# LSR_GPS_Tracker_Base_Station.net
KiCad netlist of a schematic drawn in EAGLE
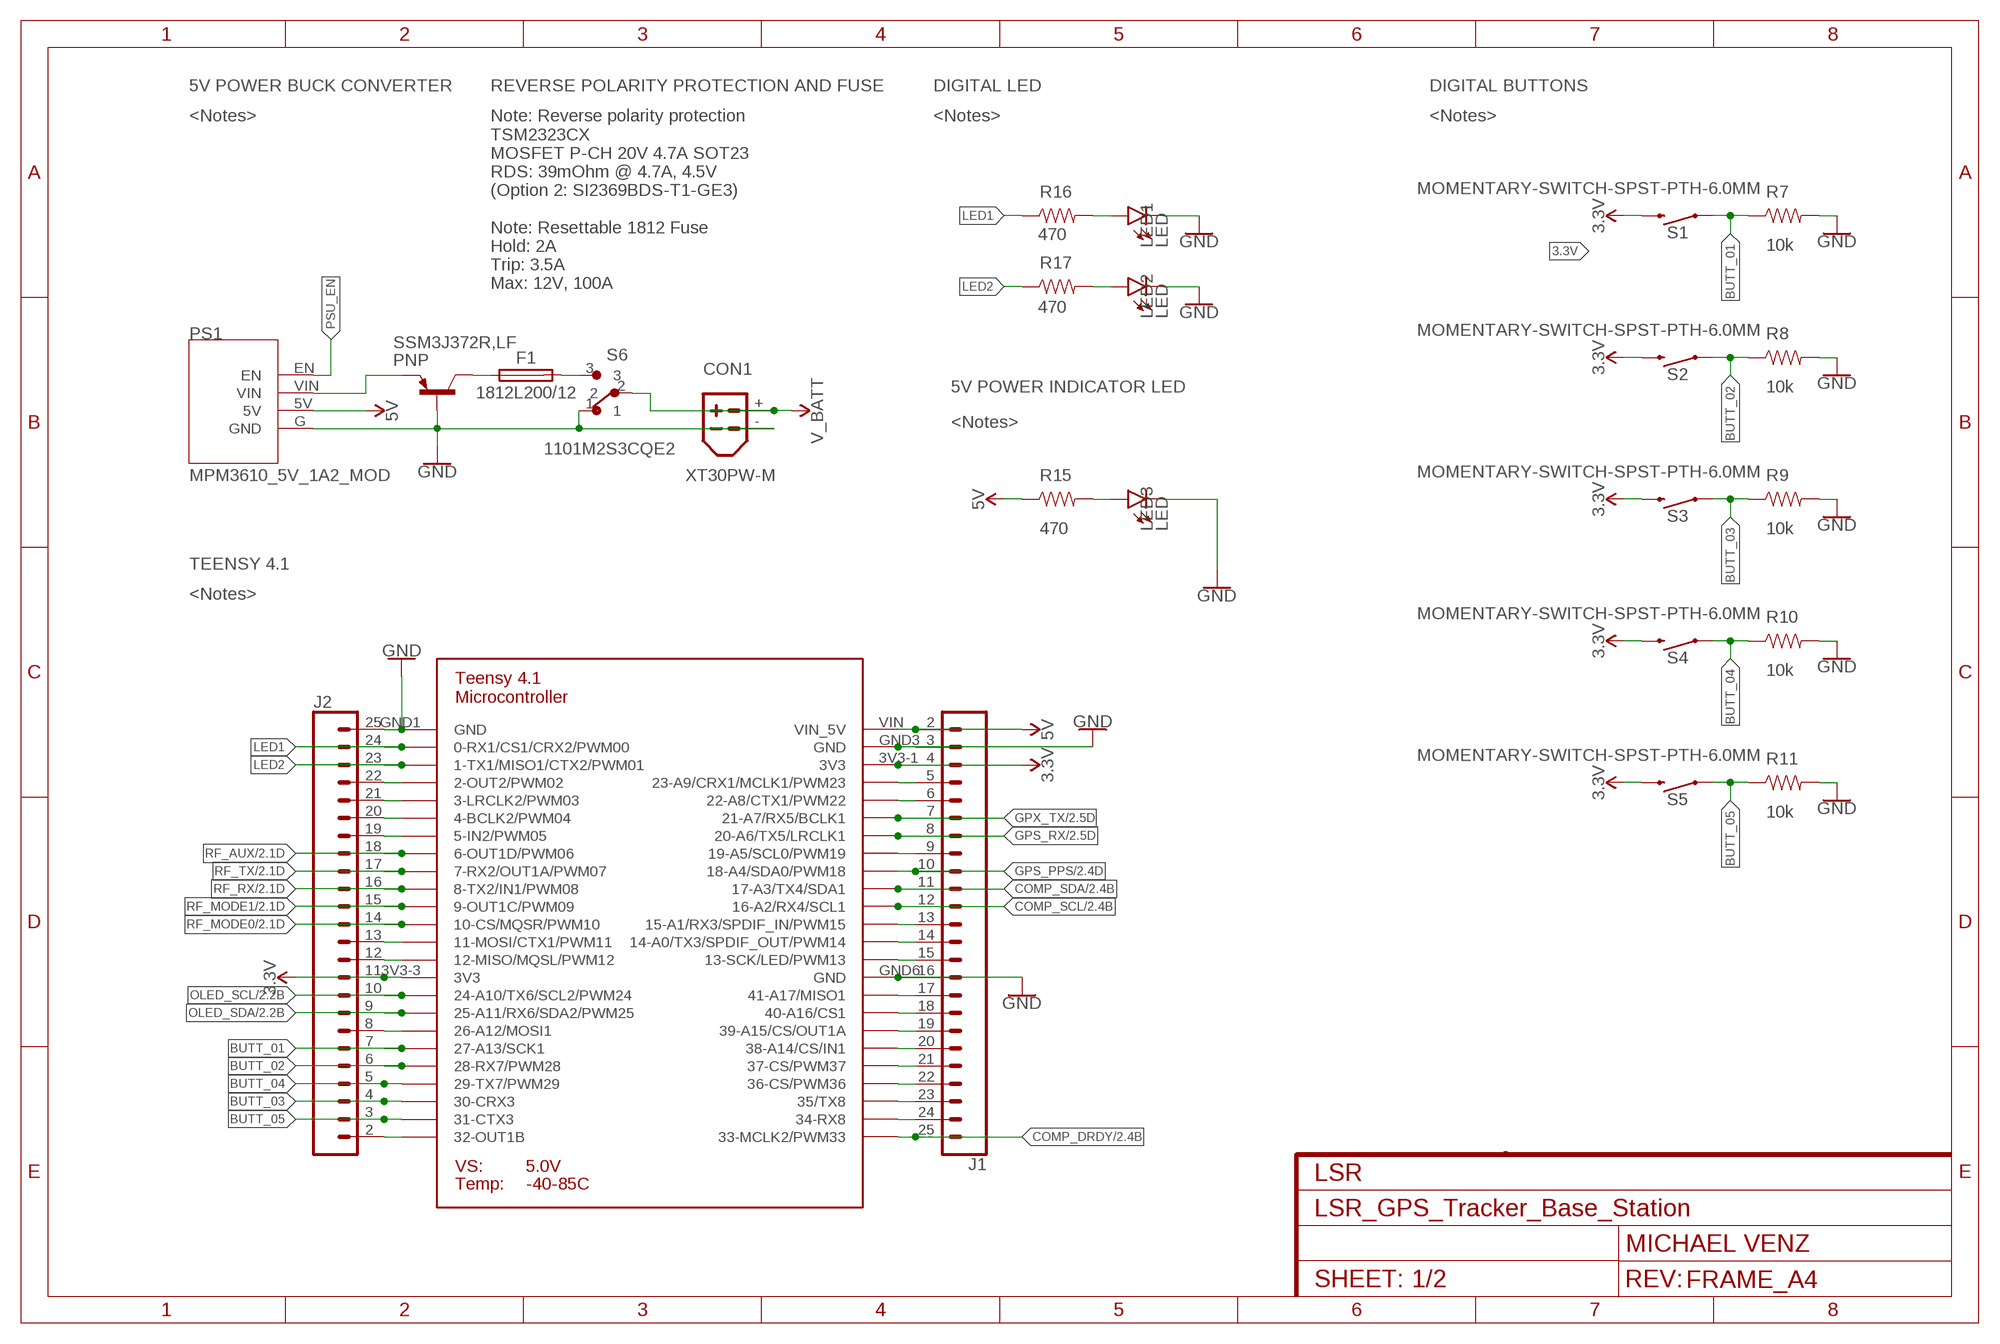
[diagram p0: schematic, sheet 1]
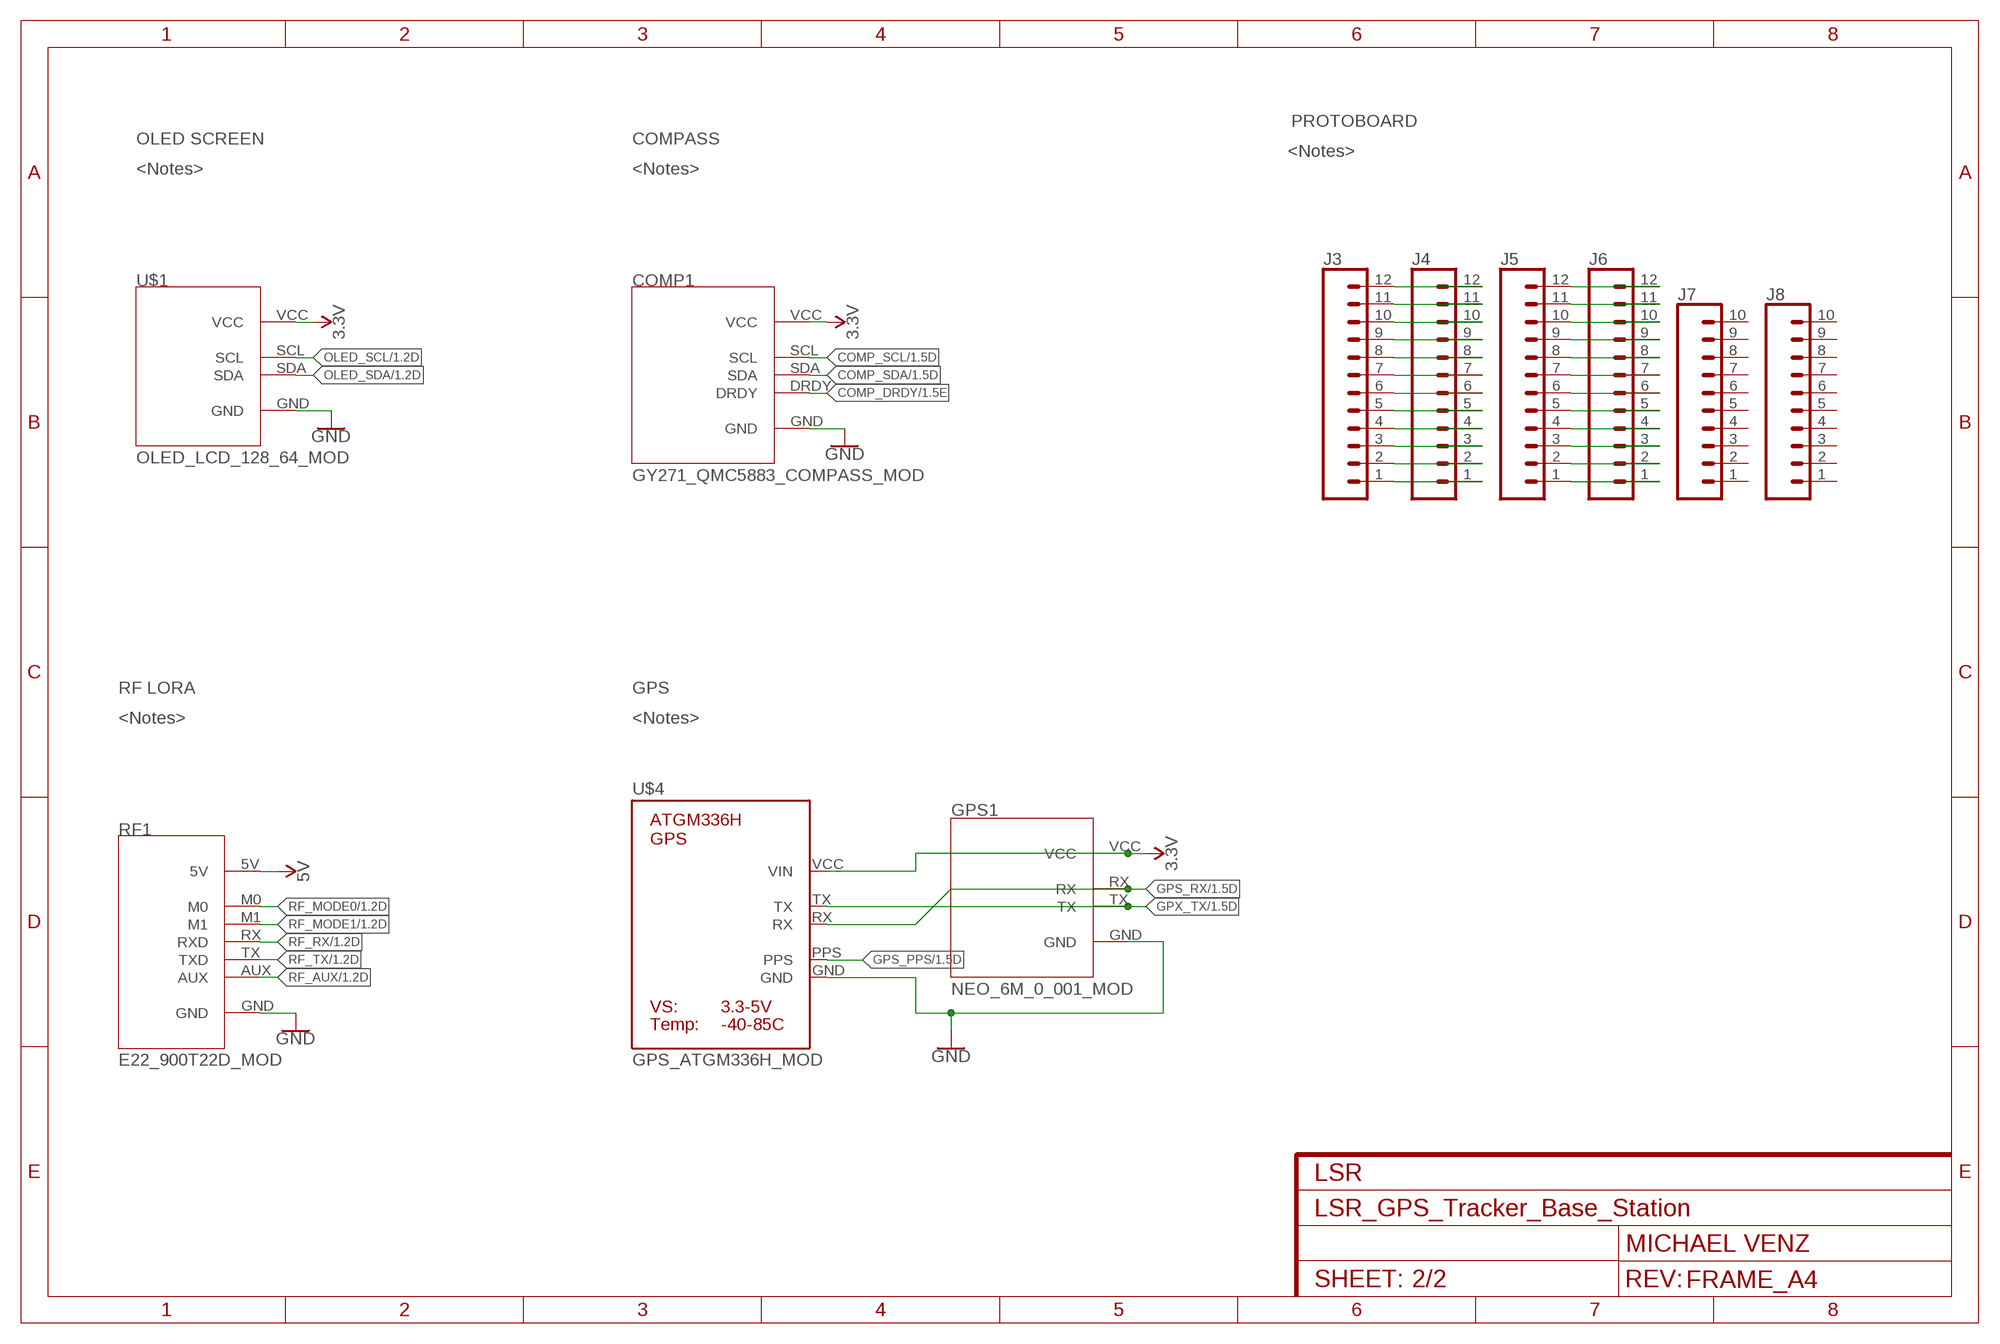
[diagram p1: schematic, sheet 2]

(export (version "E")
  (design (tool "Eeschema 10.0.6"))
  (components
    (comp (ref "CON1")
      (value "XT30PW-M")
      (footprint "eagle-import:XT30PW-PLUG")
      (libsource (lib "eagle-import") (part "XT30PW-M"))
    )
    (comp (ref "F1")
      (value "1812L200/12")
      (footprint "eagle-import:FUSC4532X125")
      (fields (field (name "MANUFACTURER") "Littlefuse"))
      (libsource (lib "eagle-import") (part "1812L200/12"))
    )
    (comp (ref "J1")
      (value "CONN_24")
      (footprint "eagle-import:1X24")
      (libsource (lib "eagle-import") (part "CONN_24"))
    )
    (comp (ref "J2")
      (value "CONN_24")
      (footprint "eagle-import:1X24")
      (libsource (lib "eagle-import") (part "CONN_24"))
    )
    (comp (ref "LED1")
      (value "LED")
      (footprint "eagle-import:0805_LED")
      (libsource (lib "eagle-import") (part "LED"))
    )
    (comp (ref "LED2")
      (value "LED")
      (footprint "eagle-import:0805_LED")
      (libsource (lib "eagle-import") (part "LED"))
    )
    (comp (ref "LED3")
      (value "LED")
      (footprint "eagle-import:0805_LED")
      (libsource (lib "eagle-import") (part "LED"))
    )
    (comp (ref "PS1")
      (value "MPM3610_5V_1A2_MOD")
      (footprint "eagle-import:MPM3610_5V_1A2_FP")
      (libsource (lib "eagle-import") (part "MPM3610_5V_1A2_MOD"))
    )
    (comp (ref "R7")
      (value "10k")
      (footprint "eagle-import:0805_RESISTOR_FP")
      (libsource (lib "eagle-import") (part "0805_RESISTOR"))
    )
    (comp (ref "R8")
      (value "10k")
      (footprint "eagle-import:0805_RESISTOR_FP")
      (libsource (lib "eagle-import") (part "0805_RESISTOR"))
    )
    (comp (ref "R9")
      (value "10k")
      (footprint "eagle-import:0805_RESISTOR_FP")
      (libsource (lib "eagle-import") (part "0805_RESISTOR"))
    )
    (comp (ref "R10")
      (value "10k")
      (footprint "eagle-import:0805_RESISTOR_FP")
      (libsource (lib "eagle-import") (part "0805_RESISTOR"))
    )
    (comp (ref "R11")
      (value "10k")
      (footprint "eagle-import:0805_RESISTOR_FP")
      (libsource (lib "eagle-import") (part "0805_RESISTOR"))
    )
    (comp (ref "R15")
      (value "470")
      (footprint "eagle-import:0805_RESISTOR_FP")
      (libsource (lib "eagle-import") (part "0805_RESISTOR"))
    )
    (comp (ref "R16")
      (value "470")
      (footprint "eagle-import:0805_RESISTOR_FP")
      (libsource (lib "eagle-import") (part "0805_RESISTOR"))
    )
    (comp (ref "R17")
      (value "470")
      (footprint "eagle-import:0805_RESISTOR_FP")
      (libsource (lib "eagle-import") (part "0805_RESISTOR"))
    )
    (comp (ref "S1")
      (value "MOMENTARY-SWITCH-SPST-PTH-6.0MM")
      (footprint "eagle-import:TACTILE_SWITCH_PTH_6.0MM")
      (libsource (lib "eagle-import") (part "MOMENTARY-SWITCH-SPST-PTH-6.0MM"))
    )
    (comp (ref "S2")
      (value "MOMENTARY-SWITCH-SPST-PTH-6.0MM")
      (footprint "eagle-import:TACTILE_SWITCH_PTH_6.0MM")
      (libsource (lib "eagle-import") (part "MOMENTARY-SWITCH-SPST-PTH-6.0MM"))
    )
    (comp (ref "S3")
      (value "MOMENTARY-SWITCH-SPST-PTH-6.0MM")
      (footprint "eagle-import:TACTILE_SWITCH_PTH_6.0MM")
      (libsource (lib "eagle-import") (part "MOMENTARY-SWITCH-SPST-PTH-6.0MM"))
    )
    (comp (ref "S4")
      (value "MOMENTARY-SWITCH-SPST-PTH-6.0MM")
      (footprint "eagle-import:TACTILE_SWITCH_PTH_6.0MM")
      (libsource (lib "eagle-import") (part "MOMENTARY-SWITCH-SPST-PTH-6.0MM"))
    )
    (comp (ref "S5")
      (value "MOMENTARY-SWITCH-SPST-PTH-6.0MM")
      (footprint "eagle-import:TACTILE_SWITCH_PTH_6.0MM")
      (libsource (lib "eagle-import") (part "MOMENTARY-SWITCH-SPST-PTH-6.0MM"))
    )
    (comp (ref "S6")
      (value "1101M2S3CQE2")
      (footprint "eagle-import:SW_1101M2S3CQE2")
      (fields (field (name "DIGI-KEY_PART_NUMBER") "CKN5001-ND") (field (name "MF") "C&K"))
      (libsource (lib "eagle-import") (part "1101M2S3CQE2"))
    )
    (comp (ref "SSM3J372R,LF")
      (value "PNP")
      (footprint "eagle-import:SOT95P237X112-3N")
      (libsource (lib "eagle-import") (part "PNPSOT23_"))
    )
    (comp (ref "U$3")
      (value "TEENSY_4_1")
      (footprint "eagle-import:TEENSY_4_1_FP")
      (libsource (lib "eagle-import") (part "TEENSY_4_1"))
    )
    (comp (ref "COMP1")
      (value "GY271_QMC5883_COMPASS_MOD")
      (footprint "eagle-import:GY271_QMC5883_COMPASS_MOD_FP")
      (libsource (lib "eagle-import") (part "GY271_QMC5883_COMPASS_MOD"))
    )
    (comp (ref "GPS1")
      (value "NEO_6M_0_001_MOD")
      (footprint "eagle-import:NEO_6M_0_001_MOD_FP")
      (libsource (lib "eagle-import") (part "NEO_6M_0_001_MOD"))
    )
    (comp (ref "J3")
      (value "CONN_12NO_SILK")
      (footprint "eagle-import:1X12_NO_SILK")
      (libsource (lib "eagle-import") (part "CONN_12NO_SILK"))
    )
    (comp (ref "J4")
      (value "CONN_12NO_SILK")
      (footprint "eagle-import:1X12_NO_SILK")
      (libsource (lib "eagle-import") (part "CONN_12NO_SILK"))
    )
    (comp (ref "J5")
      (value "CONN_12NO_SILK")
      (footprint "eagle-import:1X12_NO_SILK")
      (libsource (lib "eagle-import") (part "CONN_12NO_SILK"))
    )
    (comp (ref "J6")
      (value "CONN_12NO_SILK")
      (footprint "eagle-import:1X12_NO_SILK")
      (libsource (lib "eagle-import") (part "CONN_12NO_SILK"))
    )
    (comp (ref "J7")
      (value "CONN_10NO_SILK_PTH_FEMALE")
      (footprint "eagle-import:1X10_NO_SILK")
      (libsource (lib "eagle-import") (part "CONN_10NO_SILK_PTH_FEMALE"))
    )
    (comp (ref "J8")
      (value "CONN_10NO_SILK_PTH_FEMALE")
      (footprint "eagle-import:1X10_NO_SILK")
      (libsource (lib "eagle-import") (part "CONN_10NO_SILK_PTH_FEMALE"))
    )
    (comp (ref "RF1")
      (value "E22_900T22D_MOD")
      (footprint "eagle-import:E22_900T22D_MOD_FP")
      (libsource (lib "eagle-import") (part "E22_900T22D_MOD"))
    )
    (comp (ref "U$1")
      (value "OLED_LCD_128_64_MOD")
      (footprint "eagle-import:OLED_LCD_128_64_MOD_FP")
      (libsource (lib "eagle-import") (part "OLED_LCD_128_64_MOD"))
    )
    (comp (ref "U$4")
      (value "GPS_ATGM336H_MOD")
      (footprint "eagle-import:GPS_ATGM336H_FP")
      (libsource (lib "eagle-import") (part "GPS_ATGM336H_MOD"))
    )
  )
  (nets
    (net (code "1") (name "3.3V") (class "Default")
      (node (ref "COMP1") (pin "VCC") (pinfunction "VCC_VCC") (pintype "bidirectional"))
      (node (ref "GPS1") (pin "VCC") (pinfunction "VCC_VCC") (pintype "bidirectional"))
      (node (ref "J1") (pin "4") (pinfunction "4_4") (pintype "passive"))
      (node (ref "J2") (pin "11") (pinfunction "11_11") (pintype "passive"))
      (node (ref "S1") (pin "3") (pinfunction "2_3") (pintype "passive"))
      (node (ref "S2") (pin "3") (pinfunction "2_3") (pintype "passive"))
      (node (ref "S3") (pin "3") (pinfunction "2_3") (pintype "passive"))
      (node (ref "S4") (pin "3") (pinfunction "2_3") (pintype "passive"))
      (node (ref "S5") (pin "3") (pinfunction "2_3") (pintype "passive"))
      (node (ref "U$1") (pin "VCC") (pinfunction "VCC_VCC") (pintype "bidirectional"))
      (node (ref "U$3") (pin "3V3-1") (pinfunction "3V3_3V3-1") (pintype "bidirectional"))
      (node (ref "U$3") (pin "3V3-3") (pinfunction "3V3_3V3-3") (pintype "bidirectional"))
      (node (ref "U$4") (pin "VCC") (pinfunction "VIN_VCC") (pintype "bidirectional"))
    )
    (net (code "2") (name "5V") (class "Default")
      (node (ref "J1") (pin "2") (pinfunction "2_2") (pintype "passive"))
      (node (ref "PS1") (pin "5V") (pinfunction "5V_5V") (pintype "bidirectional"))
      (node (ref "R15") (pin "1") (pinfunction "1_1") (pintype "passive"))
      (node (ref "RF1") (pin "5V") (pinfunction "5V_5V") (pintype "bidirectional"))
      (node (ref "U$3") (pin "VIN") (pinfunction "VIN_5V_VIN") (pintype "bidirectional"))
    )
    (net (code "3") (name "BUTT_01") (class "Default")
      (node (ref "J2") (pin "7") (pinfunction "7_7") (pintype "passive"))
      (node (ref "R7") (pin "1") (pinfunction "1_1") (pintype "passive"))
      (node (ref "S1") (pin "1") (pinfunction "1_1") (pintype "passive"))
      (node (ref "U$3") (pin "27-A13/SCK1") (pinfunction "27-A13/SCK1_27-A13/SCK1") (pintype "bidirectional"))
    )
    (net (code "4") (name "BUTT_02") (class "Default")
      (node (ref "J2") (pin "6") (pinfunction "6_6") (pintype "passive"))
      (node (ref "R8") (pin "1") (pinfunction "1_1") (pintype "passive"))
      (node (ref "S2") (pin "1") (pinfunction "1_1") (pintype "passive"))
      (node (ref "U$3") (pin "28-RX7/PWM28") (pinfunction "28-RX7/PWM28_28-RX7/PWM28") (pintype "bidirectional"))
    )
    (net (code "5") (name "BUTT_03") (class "Default")
      (node (ref "J2") (pin "4") (pinfunction "4_4") (pintype "passive"))
      (node (ref "R9") (pin "1") (pinfunction "1_1") (pintype "passive"))
      (node (ref "S3") (pin "1") (pinfunction "1_1") (pintype "passive"))
      (node (ref "U$3") (pin "30-CRX3") (pinfunction "30-CRX3_30-CRX3") (pintype "bidirectional"))
    )
    (net (code "6") (name "BUTT_04") (class "Default")
      (node (ref "J2") (pin "5") (pinfunction "5_5") (pintype "passive"))
      (node (ref "R10") (pin "1") (pinfunction "1_1") (pintype "passive"))
      (node (ref "S4") (pin "1") (pinfunction "1_1") (pintype "passive"))
      (node (ref "U$3") (pin "29-TX7/PWM29") (pinfunction "29-TX7/PWM29_29-TX7/PWM29") (pintype "bidirectional"))
    )
    (net (code "7") (name "BUTT_05") (class "Default")
      (node (ref "J2") (pin "3") (pinfunction "3_3") (pintype "passive"))
      (node (ref "R11") (pin "1") (pinfunction "1_1") (pintype "passive"))
      (node (ref "S5") (pin "1") (pinfunction "1_1") (pintype "passive"))
      (node (ref "U$3") (pin "31-CTX3") (pinfunction "31-CTX3_31-CTX3") (pintype "bidirectional"))
    )
    (net (code "8") (name "COMP_DRDY") (class "Default")
      (node (ref "COMP1") (pin "DRDY") (pinfunction "DRDY_DRDY") (pintype "bidirectional"))
      (node (ref "J1") (pin "25") (pinfunction "25_25") (pintype "passive"))
      (node (ref "U$3") (pin "33-MCLK2/PWM33") (pinfunction "33-MCLK2/PWM33_33-MCLK2/PWM33") (pintype "bidirectional"))
    )
    (net (code "9") (name "COMP_SCL") (class "Default")
      (node (ref "COMP1") (pin "SCL") (pinfunction "SCL_SCL") (pintype "bidirectional"))
      (node (ref "J1") (pin "12") (pinfunction "12_12") (pintype "passive"))
      (node (ref "U$3") (pin "16-A2/RX4/SCL1") (pinfunction "16-A2/RX4/SCL1_16-A2/RX4/SCL1") (pintype "bidirectional"))
    )
    (net (code "10") (name "COMP_SDA") (class "Default")
      (node (ref "COMP1") (pin "SDA") (pinfunction "SDA_SDA") (pintype "bidirectional"))
      (node (ref "J1") (pin "11") (pinfunction "11_11") (pintype "passive"))
      (node (ref "U$3") (pin "17-A3/TX4/SDA1") (pinfunction "17-A3/TX4/SDA1_17-A3/TX4/SDA1") (pintype "bidirectional"))
    )
    (net (code "11") (name "GND") (class "Default")
      (node (ref "COMP1") (pin "GND") (pinfunction "GND_GND") (pintype "bidirectional"))
      (node (ref "CON1") (pin "-") (pinfunction "-_-") (pintype "power_in"))
      (node (ref "GPS1") (pin "GND") (pinfunction "GND_GND") (pintype "bidirectional"))
      (node (ref "J1") (pin "16") (pinfunction "16_16") (pintype "passive"))
      (node (ref "J1") (pin "3") (pinfunction "3_3") (pintype "passive"))
      (node (ref "J2") (pin "25") (pinfunction "25_25") (pintype "passive"))
      (node (ref "LED1") (pin "C") (pinfunction "C_C") (pintype "passive"))
      (node (ref "LED2") (pin "C") (pinfunction "C_C") (pintype "passive"))
      (node (ref "LED3") (pin "C") (pinfunction "C_C") (pintype "passive"))
      (node (ref "PS1") (pin "G") (pinfunction "GND_G") (pintype "bidirectional"))
      (node (ref "R10") (pin "2") (pinfunction "2_2") (pintype "passive"))
      (node (ref "R11") (pin "2") (pinfunction "2_2") (pintype "passive"))
      (node (ref "R7") (pin "2") (pinfunction "2_2") (pintype "passive"))
      (node (ref "R8") (pin "2") (pinfunction "2_2") (pintype "passive"))
      (node (ref "R9") (pin "2") (pinfunction "2_2") (pintype "passive"))
      (node (ref "RF1") (pin "GND") (pinfunction "GND_GND") (pintype "bidirectional"))
      (node (ref "S6") (pin "1") (pinfunction "1_1") (pintype "passive"))
      (node (ref "SSM3J372R,LF") (pin "1") (pinfunction "B_1") (pintype "passive"))
      (node (ref "U$1") (pin "GND") (pinfunction "GND_GND") (pintype "bidirectional"))
      (node (ref "U$3") (pin "GND1") (pinfunction "GND_GND1") (pintype "bidirectional"))
      (node (ref "U$3") (pin "GND3") (pinfunction "GND_GND3") (pintype "bidirectional"))
      (node (ref "U$3") (pin "GND6") (pinfunction "GND_GND6") (pintype "bidirectional"))
      (node (ref "U$4") (pin "GND") (pinfunction "GND_GND") (pintype "bidirectional"))
    )
    (net (code "12") (name "GPS_PPS") (class "Default")
      (node (ref "J1") (pin "10") (pinfunction "10_10") (pintype "passive"))
      (node (ref "U$3") (pin "18-A4/SDA0/PWM18") (pinfunction "18-A4/SDA0/PWM18_18-A4/SDA0/PWM18") (pintype "bidirectional"))
      (node (ref "U$4") (pin "PPS") (pinfunction "PPS_PPS") (pintype "bidirectional"))
    )
    (net (code "13") (name "GPS_RX") (class "Default")
      (node (ref "GPS1") (pin "RX") (pinfunction "RX_RX") (pintype "bidirectional"))
      (node (ref "J1") (pin "8") (pinfunction "8_8") (pintype "passive"))
      (node (ref "U$3") (pin "20-A6/TX5/LRCLK1") (pinfunction "20-A6/TX5/LRCLK1_20-A6/TX5/LRCLK1") (pintype "bidirectional"))
      (node (ref "U$4") (pin "RX") (pinfunction "RX_RX") (pintype "bidirectional"))
    )
    (net (code "14") (name "GPX_TX") (class "Default")
      (node (ref "GPS1") (pin "TX") (pinfunction "TX_TX") (pintype "bidirectional"))
      (node (ref "J1") (pin "7") (pinfunction "7_7") (pintype "passive"))
      (node (ref "U$3") (pin "21-A7/RX5/BCLK1") (pinfunction "21-A7/RX5/BCLK1_21-A7/RX5/BCLK1") (pintype "bidirectional"))
      (node (ref "U$4") (pin "TX") (pinfunction "TX_TX") (pintype "input"))
    )
    (net (code "15") (name "LED1") (class "Default")
      (node (ref "J2") (pin "24") (pinfunction "24_24") (pintype "passive"))
      (node (ref "R16") (pin "1") (pinfunction "1_1") (pintype "passive"))
      (node (ref "U$3") (pin "0-RX1/CS1/CRX2/PWM00") (pinfunction "0-RX1/CS1/CRX2/PWM00_0-RX1/CS1/CRX2/PWM00") (pintype "bidirectional"))
    )
    (net (code "16") (name "LED2") (class "Default")
      (node (ref "J2") (pin "23") (pinfunction "23_23") (pintype "passive"))
      (node (ref "R17") (pin "1") (pinfunction "1_1") (pintype "passive"))
      (node (ref "U$3") (pin "1-TX1/MISO1/CTX2/PWM01") (pinfunction "1-TX1/MISO1/CTX2/PWM01_1-TX1/MISO1/CTX2/PWM01") (pintype "bidirectional"))
    )
    (net (code "17") (name "Net-(F1-Pad2)") (class "Default")
      (node (ref "F1") (pin "2") (pinfunction "2_2") (pintype "passive"))
      (node (ref "S6") (pin "3") (pinfunction "3_3") (pintype "passive"))
    )
    (net (code "18") (name "Net-(J1-Pad5)") (class "Default")
      (node (ref "J1") (pin "5") (pinfunction "5_5") (pintype "passive"))
      (node (ref "U$3") (pin "23-A9/CRX1/MCLK1/PWM23") (pinfunction "23-A9/CRX1/MCLK1/PWM23_23-A9/CRX1/MCLK1/PWM23") (pintype "bidirectional"))
    )
    (net (code "19") (name "Net-(J1-Pad6)") (class "Default")
      (node (ref "J1") (pin "6") (pinfunction "6_6") (pintype "passive"))
      (node (ref "U$3") (pin "22-A8/CTX1/PWM22") (pinfunction "22-A8/CTX1/PWM22_22-A8/CTX1/PWM22") (pintype "bidirectional"))
    )
    (net (code "20") (name "Net-(J1-Pad9)") (class "Default")
      (node (ref "J1") (pin "9") (pinfunction "9_9") (pintype "passive"))
      (node (ref "U$3") (pin "19-A5/SCL0/PWM19") (pinfunction "19-A5/SCL0/PWM19_19-A5/SCL0/PWM19") (pintype "bidirectional"))
    )
    (net (code "21") (name "Net-(J1-Pad13)") (class "Default")
      (node (ref "J1") (pin "13") (pinfunction "13_13") (pintype "passive"))
      (node (ref "U$3") (pin "15-A1/RX3/SPDIF_IN/PWM15") (pinfunction "15-A1/RX3/SPDIF_IN/PWM15_15-A1/RX3/SPDIF_IN/PWM15") (pintype "bidirectional"))
    )
    (net (code "22") (name "Net-(J1-Pad14)") (class "Default")
      (node (ref "J1") (pin "14") (pinfunction "14_14") (pintype "passive"))
      (node (ref "U$3") (pin "14-A0/TX3/SPDIF_OUT/PWM14") (pinfunction "14-A0/TX3/SPDIF_OUT/PWM14_14-A0/TX3/SPDIF_OUT/PWM14") (pintype "bidirectional"))
    )
    (net (code "23") (name "Net-(J1-Pad15)") (class "Default")
      (node (ref "J1") (pin "15") (pinfunction "15_15") (pintype "passive"))
      (node (ref "U$3") (pin "13-SCK/LED/PWM13") (pinfunction "13-SCK/LED/PWM13_13-SCK/LED/PWM13") (pintype "bidirectional"))
    )
    (net (code "24") (name "Net-(J1-Pad17)") (class "Default")
      (node (ref "J1") (pin "17") (pinfunction "17_17") (pintype "passive"))
      (node (ref "U$3") (pin "41-A17/MISO1") (pinfunction "41-A17/MISO1_41-A17/MISO1") (pintype "bidirectional"))
    )
    (net (code "25") (name "Net-(J1-Pad18)") (class "Default")
      (node (ref "J1") (pin "18") (pinfunction "18_18") (pintype "passive"))
      (node (ref "U$3") (pin "40-A16/CS1") (pinfunction "40-A16/CS1_40-A16/CS1") (pintype "bidirectional"))
    )
    (net (code "26") (name "Net-(J1-Pad19)") (class "Default")
      (node (ref "J1") (pin "19") (pinfunction "19_19") (pintype "passive"))
      (node (ref "U$3") (pin "39-A15/CS/OUT1A") (pinfunction "39-A15/CS/OUT1A_39-A15/CS/OUT1A") (pintype "bidirectional"))
    )
    (net (code "27") (name "Net-(J1-Pad20)") (class "Default")
      (node (ref "J1") (pin "20") (pinfunction "20_20") (pintype "passive"))
      (node (ref "U$3") (pin "38-A14/CS/IN1") (pinfunction "38-A14/CS/IN1_38-A14/CS/IN1") (pintype "bidirectional"))
    )
    (net (code "28") (name "Net-(J1-Pad21)") (class "Default")
      (node (ref "J1") (pin "21") (pinfunction "21_21") (pintype "passive"))
      (node (ref "U$3") (pin "37-CS/PWM37") (pinfunction "37-CS/PWM37_37-CS/PWM37") (pintype "bidirectional"))
    )
    (net (code "29") (name "Net-(J1-Pad22)") (class "Default")
      (node (ref "J1") (pin "22") (pinfunction "22_22") (pintype "passive"))
      (node (ref "U$3") (pin "36-CS/PWM36") (pinfunction "36-CS/PWM36_36-CS/PWM36") (pintype "bidirectional"))
    )
    (net (code "30") (name "Net-(J1-Pad24)") (class "Default")
      (node (ref "J1") (pin "24") (pinfunction "24_24") (pintype "passive"))
      (node (ref "U$3") (pin "34-RX8") (pinfunction "34-RX8_34-RX8") (pintype "bidirectional"))
    )
    (net (code "31") (name "Net-(J2-Pad2)") (class "Default")
      (node (ref "J2") (pin "2") (pinfunction "2_2") (pintype "passive"))
      (node (ref "U$3") (pin "32-OUT1B") (pinfunction "32-OUT1B_32-OUT1B") (pintype "bidirectional"))
    )
    (net (code "32") (name "Net-(J2-Pad8)") (class "Default")
      (node (ref "J2") (pin "8") (pinfunction "8_8") (pintype "passive"))
      (node (ref "U$3") (pin "26-A12/MOSI1") (pinfunction "26-A12/MOSI1_26-A12/MOSI1") (pintype "bidirectional"))
    )
    (net (code "33") (name "Net-(J2-Pad12)") (class "Default")
      (node (ref "J2") (pin "12") (pinfunction "12_12") (pintype "passive"))
      (node (ref "U$3") (pin "12-MISO/MQSL/PWM12") (pinfunction "12-MISO/MQSL/PWM12_12-MISO/MQSL/PWM12") (pintype "bidirectional"))
    )
    (net (code "34") (name "Net-(J2-Pad13)") (class "Default")
      (node (ref "J2") (pin "13") (pinfunction "13_13") (pintype "passive"))
      (node (ref "U$3") (pin "11-MOSI/CTX1/PWM11") (pinfunction "11-MOSI/CTX1/PWM11_11-MOSI/CTX1/PWM11") (pintype "bidirectional"))
    )
    (net (code "35") (name "Net-(J2-Pad19)") (class "Default")
      (node (ref "J2") (pin "19") (pinfunction "19_19") (pintype "passive"))
      (node (ref "U$3") (pin "5-IN2/PWM05") (pinfunction "5-IN2/PWM05_5-IN2/PWM05") (pintype "bidirectional"))
    )
    (net (code "36") (name "Net-(J2-Pad20)") (class "Default")
      (node (ref "J2") (pin "20") (pinfunction "20_20") (pintype "passive"))
      (node (ref "U$3") (pin "4-BCLK2/PWM04") (pinfunction "4-BCLK2/PWM04_4-BCLK2/PWM04") (pintype "bidirectional"))
    )
    (net (code "37") (name "Net-(J2-Pad21)") (class "Default")
      (node (ref "J2") (pin "21") (pinfunction "21_21") (pintype "passive"))
      (node (ref "U$3") (pin "3-LRCLK2/PWM03") (pinfunction "3-LRCLK2/PWM03_3-LRCLK2/PWM03") (pintype "bidirectional"))
    )
    (net (code "38") (name "Net-(J2-Pad22)") (class "Default")
      (node (ref "J2") (pin "22") (pinfunction "22_22") (pintype "passive"))
      (node (ref "U$3") (pin "2-OUT2/PWM02") (pinfunction "2-OUT2/PWM02_2-OUT2/PWM02") (pintype "bidirectional"))
    )
    (net (code "39") (name "Net-(J3-Pad1)") (class "Default")
      (node (ref "J3") (pin "1") (pinfunction "1_1") (pintype "passive"))
      (node (ref "J4") (pin "1") (pinfunction "1_1") (pintype "passive"))
    )
    (net (code "40") (name "Net-(J3-Pad2)") (class "Default")
      (node (ref "J3") (pin "2") (pinfunction "2_2") (pintype "passive"))
      (node (ref "J4") (pin "2") (pinfunction "2_2") (pintype "passive"))
    )
    (net (code "41") (name "Net-(J3-Pad3)") (class "Default")
      (node (ref "J3") (pin "3") (pinfunction "3_3") (pintype "passive"))
      (node (ref "J4") (pin "3") (pinfunction "3_3") (pintype "passive"))
    )
    (net (code "42") (name "Net-(J3-Pad4)") (class "Default")
      (node (ref "J3") (pin "4") (pinfunction "4_4") (pintype "passive"))
      (node (ref "J4") (pin "4") (pinfunction "4_4") (pintype "passive"))
    )
    (net (code "43") (name "Net-(J3-Pad5)") (class "Default")
      (node (ref "J3") (pin "5") (pinfunction "5_5") (pintype "passive"))
      (node (ref "J4") (pin "5") (pinfunction "5_5") (pintype "passive"))
    )
    (net (code "44") (name "Net-(J3-Pad6)") (class "Default")
      (node (ref "J3") (pin "6") (pinfunction "6_6") (pintype "passive"))
      (node (ref "J4") (pin "6") (pinfunction "6_6") (pintype "passive"))
    )
    (net (code "45") (name "Net-(J3-Pad7)") (class "Default")
      (node (ref "J3") (pin "7") (pinfunction "7_7") (pintype "passive"))
      (node (ref "J4") (pin "7") (pinfunction "7_7") (pintype "passive"))
    )
    (net (code "46") (name "Net-(J3-Pad8)") (class "Default")
      (node (ref "J3") (pin "8") (pinfunction "8_8") (pintype "passive"))
      (node (ref "J4") (pin "8") (pinfunction "8_8") (pintype "passive"))
    )
    (net (code "47") (name "Net-(J3-Pad9)") (class "Default")
      (node (ref "J3") (pin "9") (pinfunction "9_9") (pintype "passive"))
      (node (ref "J4") (pin "9") (pinfunction "9_9") (pintype "passive"))
    )
    (net (code "48") (name "Net-(J3-Pad10)") (class "Default")
      (node (ref "J3") (pin "10") (pinfunction "10_10") (pintype "passive"))
      (node (ref "J4") (pin "10") (pinfunction "10_10") (pintype "passive"))
    )
    (net (code "49") (name "Net-(J3-Pad11)") (class "Default")
      (node (ref "J3") (pin "11") (pinfunction "11_11") (pintype "passive"))
      (node (ref "J4") (pin "11") (pinfunction "11_11") (pintype "passive"))
    )
    (net (code "50") (name "Net-(J3-Pad12)") (class "Default")
      (node (ref "J3") (pin "12") (pinfunction "12_12") (pintype "passive"))
      (node (ref "J4") (pin "12") (pinfunction "12_12") (pintype "passive"))
    )
    (net (code "51") (name "Net-(J5-Pad1)") (class "Default")
      (node (ref "J5") (pin "1") (pinfunction "1_1") (pintype "passive"))
      (node (ref "J6") (pin "1") (pinfunction "1_1") (pintype "passive"))
    )
    (net (code "52") (name "Net-(J5-Pad2)") (class "Default")
      (node (ref "J5") (pin "2") (pinfunction "2_2") (pintype "passive"))
      (node (ref "J6") (pin "2") (pinfunction "2_2") (pintype "passive"))
    )
    (net (code "53") (name "Net-(J5-Pad3)") (class "Default")
      (node (ref "J5") (pin "3") (pinfunction "3_3") (pintype "passive"))
      (node (ref "J6") (pin "3") (pinfunction "3_3") (pintype "passive"))
    )
    (net (code "54") (name "Net-(J5-Pad4)") (class "Default")
      (node (ref "J5") (pin "4") (pinfunction "4_4") (pintype "passive"))
      (node (ref "J6") (pin "4") (pinfunction "4_4") (pintype "passive"))
    )
    (net (code "55") (name "Net-(J5-Pad5)") (class "Default")
      (node (ref "J5") (pin "5") (pinfunction "5_5") (pintype "passive"))
      (node (ref "J6") (pin "5") (pinfunction "5_5") (pintype "passive"))
    )
    (net (code "56") (name "Net-(J5-Pad6)") (class "Default")
      (node (ref "J5") (pin "6") (pinfunction "6_6") (pintype "passive"))
      (node (ref "J6") (pin "6") (pinfunction "6_6") (pintype "passive"))
    )
    (net (code "57") (name "Net-(J5-Pad7)") (class "Default")
      (node (ref "J5") (pin "7") (pinfunction "7_7") (pintype "passive"))
      (node (ref "J6") (pin "7") (pinfunction "7_7") (pintype "passive"))
    )
    (net (code "58") (name "Net-(J5-Pad8)") (class "Default")
      (node (ref "J5") (pin "8") (pinfunction "8_8") (pintype "passive"))
      (node (ref "J6") (pin "8") (pinfunction "8_8") (pintype "passive"))
    )
    (net (code "59") (name "Net-(J5-Pad9)") (class "Default")
      (node (ref "J5") (pin "9") (pinfunction "9_9") (pintype "passive"))
      (node (ref "J6") (pin "9") (pinfunction "9_9") (pintype "passive"))
    )
    (net (code "60") (name "Net-(J5-Pad10)") (class "Default")
      (node (ref "J5") (pin "10") (pinfunction "10_10") (pintype "passive"))
      (node (ref "J6") (pin "10") (pinfunction "10_10") (pintype "passive"))
    )
    (net (code "61") (name "Net-(J5-Pad11)") (class "Default")
      (node (ref "J5") (pin "11") (pinfunction "11_11") (pintype "passive"))
      (node (ref "J6") (pin "11") (pinfunction "11_11") (pintype "passive"))
    )
    (net (code "62") (name "Net-(J5-Pad12)") (class "Default")
      (node (ref "J5") (pin "12") (pinfunction "12_12") (pintype "passive"))
      (node (ref "J6") (pin "12") (pinfunction "12_12") (pintype "passive"))
    )
    (net (code "63") (name "Net-(LED1-PadA)") (class "Default")
      (node (ref "LED1") (pin "A") (pinfunction "A_A") (pintype "passive"))
      (node (ref "R16") (pin "2") (pinfunction "2_2") (pintype "passive"))
    )
    (net (code "64") (name "Net-(LED2-PadA)") (class "Default")
      (node (ref "LED2") (pin "A") (pinfunction "A_A") (pintype "passive"))
      (node (ref "R17") (pin "2") (pinfunction "2_2") (pintype "passive"))
    )
    (net (code "65") (name "Net-(LED3-PadA)") (class "Default")
      (node (ref "LED3") (pin "A") (pinfunction "A_A") (pintype "passive"))
      (node (ref "R15") (pin "2") (pinfunction "2_2") (pintype "passive"))
    )
    (net (code "66") (name "Net-(SSM3J372R,LF-C)") (class "Default")
      (node (ref "F1") (pin "1") (pinfunction "1_1") (pintype "passive"))
      (node (ref "SSM3J372R,LF") (pin "3") (pinfunction "C_3") (pintype "passive"))
    )
    (net (code "67") (name "Net-(SSM3J372R,LF-E)") (class "Default")
      (node (ref "PS1") (pin "VIN") (pinfunction "VIN_VIN") (pintype "bidirectional"))
      (node (ref "SSM3J372R,LF") (pin "2") (pinfunction "E_2") (pintype "passive"))
    )
    (net (code "68") (name "Net-(U$3-35{slash}TX8)") (class "Default")
      (node (ref "J1") (pin "23") (pinfunction "23_23") (pintype "passive"))
      (node (ref "U$3") (pin "35-TX8") (pinfunction "35/TX8_35-TX8") (pintype "bidirectional"))
    )
    (net (code "69") (name "OLED_SCL") (class "Default")
      (node (ref "J2") (pin "10") (pinfunction "10_10") (pintype "passive"))
      (node (ref "U$1") (pin "SCL") (pinfunction "SCL_SCL") (pintype "bidirectional"))
      (node (ref "U$3") (pin "24-A10/TX6/SCL2/PWM24") (pinfunction "24-A10/TX6/SCL2/PWM24_24-A10/TX6/SCL2/PWM24") (pintype "bidirectional"))
    )
    (net (code "70") (name "OLED_SDA") (class "Default")
      (node (ref "J2") (pin "9") (pinfunction "9_9") (pintype "passive"))
      (node (ref "U$1") (pin "SDA") (pinfunction "SDA_SDA") (pintype "bidirectional"))
      (node (ref "U$3") (pin "25-A11/RX6/SDA2/PWM25") (pinfunction "25-A11/RX6/SDA2/PWM25_25-A11/RX6/SDA2/PWM25") (pintype "bidirectional"))
    )
    (net (code "71") (name "PSU_EN") (class "Default")
      (node (ref "PS1") (pin "EN") (pinfunction "EN_EN") (pintype "bidirectional"))
    )
    (net (code "72") (name "RF_AUX") (class "Default")
      (node (ref "J2") (pin "18") (pinfunction "18_18") (pintype "passive"))
      (node (ref "RF1") (pin "AUX") (pinfunction "AUX_AUX") (pintype "bidirectional"))
      (node (ref "U$3") (pin "6-OUT1D/PWM06") (pinfunction "6-OUT1D/PWM06_6-OUT1D/PWM06") (pintype "bidirectional"))
    )
    (net (code "73") (name "RF_MODE0") (class "Default")
      (node (ref "J2") (pin "14") (pinfunction "14_14") (pintype "passive"))
      (node (ref "RF1") (pin "M0") (pinfunction "M0_M0") (pintype "bidirectional"))
      (node (ref "U$3") (pin "10-CS\\MQSR/PWM10") (pinfunction "10-CS/MQSR/PWM10_10-CS\\MQSR/PWM10") (pintype "bidirectional"))
    )
    (net (code "74") (name "RF_MODE1") (class "Default")
      (node (ref "J2") (pin "15") (pinfunction "15_15") (pintype "passive"))
      (node (ref "RF1") (pin "M1") (pinfunction "M1_M1") (pintype "bidirectional"))
      (node (ref "U$3") (pin "9-OUT1C/PWM09") (pinfunction "9-OUT1C/PWM09_9-OUT1C/PWM09") (pintype "bidirectional"))
    )
    (net (code "75") (name "RF_RX") (class "Default")
      (node (ref "J2") (pin "16") (pinfunction "16_16") (pintype "passive"))
      (node (ref "RF1") (pin "RX") (pinfunction "RXD_RX") (pintype "bidirectional"))
      (node (ref "U$3") (pin "8-TX2/IN1/PWM08") (pinfunction "8-TX2/IN1/PWM08_8-TX2/IN1/PWM08") (pintype "bidirectional"))
    )
    (net (code "76") (name "RF_TX") (class "Default")
      (node (ref "J2") (pin "17") (pinfunction "17_17") (pintype "passive"))
      (node (ref "RF1") (pin "TX") (pinfunction "TXD_TX") (pintype "bidirectional"))
      (node (ref "U$3") (pin "7-RX2/OUT1A/PWM07") (pinfunction "7-RX2/OUT1A/PWM07_7-RX2/OUT1A/PWM07") (pintype "bidirectional"))
    )
    (net (code "77") (name "V_BATT") (class "Default")
      (node (ref "CON1") (pin "+") (pinfunction "+_+") (pintype "power_in"))
      (node (ref "S6") (pin "2") (pinfunction "2_2") (pintype "passive"))
    )
    (net (code "78") (name "unconnected-(J7-Pad1)") (class "Default")
      (node (ref "J7") (pin "1") (pinfunction "1_1") (pintype "passive"))
    )
    (net (code "79") (name "unconnected-(J7-Pad2)") (class "Default")
      (node (ref "J7") (pin "2") (pinfunction "2_2") (pintype "passive"))
    )
    (net (code "80") (name "unconnected-(J7-Pad3)") (class "Default")
      (node (ref "J7") (pin "3") (pinfunction "3_3") (pintype "passive"))
    )
    (net (code "81") (name "unconnected-(J7-Pad4)") (class "Default")
      (node (ref "J7") (pin "4") (pinfunction "4_4") (pintype "passive"))
    )
    (net (code "82") (name "unconnected-(J7-Pad5)") (class "Default")
      (node (ref "J7") (pin "5") (pinfunction "5_5") (pintype "passive"))
    )
    (net (code "83") (name "unconnected-(J7-Pad6)") (class "Default")
      (node (ref "J7") (pin "6") (pinfunction "6_6") (pintype "passive"))
    )
    (net (code "84") (name "unconnected-(J7-Pad7)") (class "Default")
      (node (ref "J7") (pin "7") (pinfunction "7_7") (pintype "passive"))
    )
    (net (code "85") (name "unconnected-(J7-Pad8)") (class "Default")
      (node (ref "J7") (pin "8") (pinfunction "8_8") (pintype "passive"))
    )
    (net (code "86") (name "unconnected-(J7-Pad9)") (class "Default")
      (node (ref "J7") (pin "9") (pinfunction "9_9") (pintype "passive"))
    )
    (net (code "87") (name "unconnected-(J7-Pad10)") (class "Default")
      (node (ref "J7") (pin "10") (pinfunction "10_10") (pintype "passive"))
    )
    (net (code "88") (name "unconnected-(J8-Pad1)") (class "Default")
      (node (ref "J8") (pin "1") (pinfunction "1_1") (pintype "passive"))
    )
    (net (code "89") (name "unconnected-(J8-Pad2)") (class "Default")
      (node (ref "J8") (pin "2") (pinfunction "2_2") (pintype "passive"))
    )
    (net (code "90") (name "unconnected-(J8-Pad3)") (class "Default")
      (node (ref "J8") (pin "3") (pinfunction "3_3") (pintype "passive"))
    )
    (net (code "91") (name "unconnected-(J8-Pad4)") (class "Default")
      (node (ref "J8") (pin "4") (pinfunction "4_4") (pintype "passive"))
    )
    (net (code "92") (name "unconnected-(J8-Pad5)") (class "Default")
      (node (ref "J8") (pin "5") (pinfunction "5_5") (pintype "passive"))
    )
    (net (code "93") (name "unconnected-(J8-Pad6)") (class "Default")
      (node (ref "J8") (pin "6") (pinfunction "6_6") (pintype "passive"))
    )
    (net (code "94") (name "unconnected-(J8-Pad7)") (class "Default")
      (node (ref "J8") (pin "7") (pinfunction "7_7") (pintype "passive"))
    )
    (net (code "95") (name "unconnected-(J8-Pad8)") (class "Default")
      (node (ref "J8") (pin "8") (pinfunction "8_8") (pintype "passive"))
    )
    (net (code "96") (name "unconnected-(J8-Pad9)") (class "Default")
      (node (ref "J8") (pin "9") (pinfunction "9_9") (pintype "passive"))
    )
    (net (code "97") (name "unconnected-(J8-Pad10)") (class "Default")
      (node (ref "J8") (pin "10") (pinfunction "10_10") (pintype "passive"))
    )
  )
)
